# Proto1.net
KiCad netlist of a schematic drawn in EAGLE
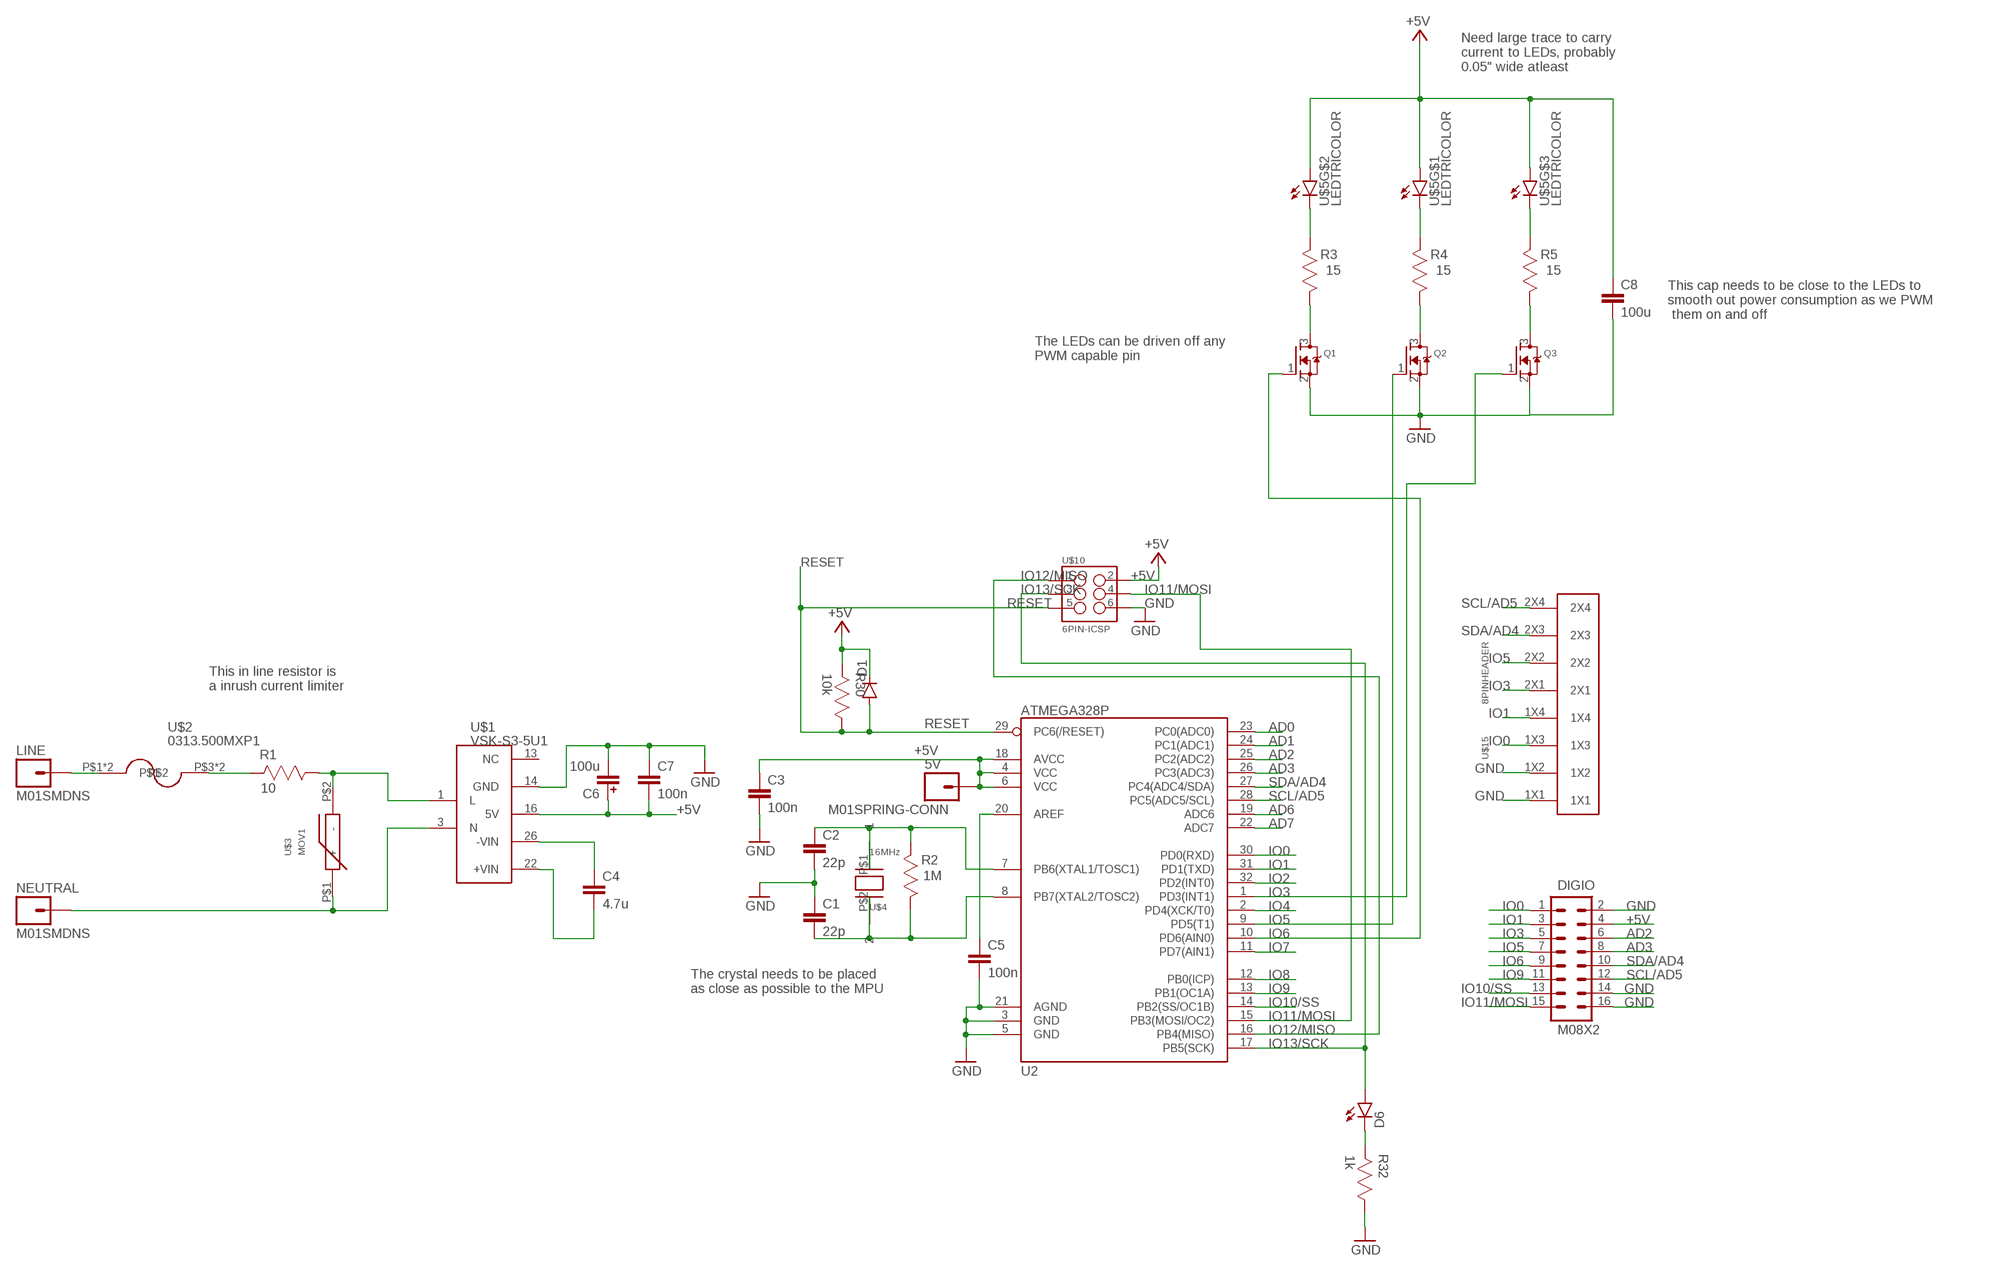
[diagram p0: schematic, sheet 1]

(export (version "E")
  (design (tool "Eeschema 10.0.6"))
  (components
    (comp (ref "5V")
      (value "M01SPRING-CONN")
      (footprint "eagle-import:SPRING-CONNECTOR")
      (libsource (lib "eagle-import") (part "M01SPRING-CONN"))
    )
    (comp (ref "C1")
      (value "22p")
      (footprint "eagle-import:0603-CAP")
      (libsource (lib "eagle-import") (part "CAP0603-CAP"))
    )
    (comp (ref "C2")
      (value "22p")
      (footprint "eagle-import:0603-CAP")
      (libsource (lib "eagle-import") (part "CAP0603-CAP"))
    )
    (comp (ref "C3")
      (value "100n")
      (footprint "eagle-import:0603-CAP")
      (libsource (lib "eagle-import") (part "CAP0603-CAP"))
    )
    (comp (ref "C4")
      (value "4.7u")
      (footprint "eagle-import:0603-CAP")
      (libsource (lib "eagle-import") (part "CAP0603-CAP"))
    )
    (comp (ref "C5")
      (value "100n")
      (footprint "eagle-import:0603-CAP")
      (libsource (lib "eagle-import") (part "CAP0603-CAP"))
    )
    (comp (ref "C6")
      (value "100u")
      (footprint "eagle-import:WXSERIES-SMDCAP")
      (libsource (lib "eagle-import") (part "SMDCAP1"))
    )
    (comp (ref "C7")
      (value "100n")
      (footprint "eagle-import:0603-CAP")
      (libsource (lib "eagle-import") (part "CAP0603-CAP"))
    )
    (comp (ref "C8")
      (value "100u")
      (footprint "eagle-import:0603-CAP")
      (libsource (lib "eagle-import") (part "CAP0603-CAP"))
    )
    (comp (ref "D1")
      (value "DIODE1N4148")
      (footprint "eagle-import:DIODE-1N4148")
      (libsource (lib "eagle-import") (part "DIODE1N4148"))
    )
    (comp (ref "D6")
      (value "LED-YELLOW0603")
      (footprint "eagle-import:LED-0603")
      (libsource (lib "eagle-import") (part "LED-YELLOW0603"))
    )
    (comp (ref "DIGIO")
      (value "M08X2")
      (footprint "eagle-import:2X8")
      (libsource (lib "eagle-import") (part "M08X2"))
    )
    (comp (ref "LINE")
      (value "M01SMDNS")
      (footprint "eagle-import:1X01NS")
      (libsource (lib "eagle-import") (part "M01SMDNS"))
    )
    (comp (ref "NEUTRAL")
      (value "M01SMDNS")
      (footprint "eagle-import:1X01NS")
      (libsource (lib "eagle-import") (part "M01SMDNS"))
    )
    (comp (ref "Q1")
      (value "MOSFET-NREFLOW")
      (footprint "eagle-import:SOT23")
      (libsource (lib "eagle-import") (part "MOSFET-NREFLOW"))
    )
    (comp (ref "Q2")
      (value "MOSFET-NREFLOW")
      (footprint "eagle-import:SOT23")
      (libsource (lib "eagle-import") (part "MOSFET-NREFLOW"))
    )
    (comp (ref "Q3")
      (value "MOSFET-NREFLOW")
      (footprint "eagle-import:SOT23")
      (libsource (lib "eagle-import") (part "MOSFET-NREFLOW"))
    )
    (comp (ref "R1")
      (value "10")
      (footprint "eagle-import:0603RESISTOR")
      (fields (field (name "MPN") "CRCW06031K21FKEA") (field (name "TOLERANCE") "± 1.0 %"))
      (libsource (lib "eagle-import") (part "0603RESISTOR1"))
    )
    (comp (ref "R2")
      (value "1M")
      (footprint "eagle-import:0603RESISTOR")
      (fields (field (name "MPN") "CRCW06031K21FKEA") (field (name "TOLERANCE") "± 1.0 %"))
      (libsource (lib "eagle-import") (part "0603RESISTOR1"))
    )
    (comp (ref "R3")
      (value "15")
      (footprint "eagle-import:0603RESISTOR")
      (fields (field (name "MPN") "CRCW06031K21FKEA") (field (name "TOLERANCE") "± 1.0 %"))
      (libsource (lib "eagle-import") (part "0603RESISTOR1"))
    )
    (comp (ref "R4")
      (value "15")
      (footprint "eagle-import:0603RESISTOR")
      (fields (field (name "MPN") "CRCW06031K21FKEA") (field (name "TOLERANCE") "± 1.0 %"))
      (libsource (lib "eagle-import") (part "0603RESISTOR1"))
    )
    (comp (ref "R5")
      (value "15")
      (footprint "eagle-import:0603RESISTOR")
      (fields (field (name "MPN") "CRCW06031K21FKEA") (field (name "TOLERANCE") "± 1.0 %"))
      (libsource (lib "eagle-import") (part "0603RESISTOR1"))
    )
    (comp (ref "R30")
      (value "10k")
      (footprint "eagle-import:0603RESISTOR")
      (fields (field (name "MPN") "CRCW06031K21FKEA") (field (name "TOLERANCE") "± 1.0 %"))
      (libsource (lib "eagle-import") (part "0603RESISTOR1"))
    )
    (comp (ref "R32")
      (value "1k")
      (footprint "eagle-import:0603RESISTOR")
      (fields (field (name "MPN") "CRCW06031K21FKEA") (field (name "TOLERANCE") "± 1.0 %"))
      (libsource (lib "eagle-import") (part "0603RESISTOR1"))
    )
    (comp (ref "U$1")
      (value "VSK-S3-5U1")
      (footprint "eagle-import:VSK-S3-DCAC")
      (libsource (lib "eagle-import") (part "VSK-S3-5U1"))
    )
    (comp (ref "U$2")
      (value "0313.500MXP1")
      (footprint "eagle-import:FUSEHOLDER0.25IN")
      (libsource (lib "eagle-import") (part "0313.500MXP1"))
    )
    (comp (ref "U$3")
      (value "MOV1")
      (footprint "eagle-import:MOV")
      (libsource (lib "eagle-import") (part "MOV1"))
    )
    (comp (ref "U$4")
      (value "16MHz")
      (footprint "eagle-import:SMDCRYSTAL")
      (libsource (lib "eagle-import") (part "SMDCRYSTAL"))
    )
    (comp (ref "U$5")
      (value "LEDTRICOLOR")
      (footprint "eagle-import:TRICOLORLED")
      (libsource (lib "eagle-import") (part "LEDTRICOLOR"))
    )
    (comp (ref "U$10")
      (value "6PIN-ICSP")
      (footprint "eagle-import:2X3-ICSP")
      (libsource (lib "eagle-import") (part "6PIN-ICSP"))
    )
    (comp (ref "U$15")
      (value "8PINHEADER")
      (footprint "eagle-import:HEADERSMDRIGHTANGLE4X2")
      (libsource (lib "eagle-import") (part "8PINHEADER"))
    )
    (comp (ref "U2")
      (value "ATMEGA328P")
      (footprint "eagle-import:TQFP32-08")
      (libsource (lib "eagle-import") (part "ATMEGA328_SMT"))
    )
  )
  (nets
    (net (code "1") (name "+5V") (class "Default")
      (node (ref "5V") (pin "P$2") (pinfunction "1_P$2") (pintype "passive"))
      (node (ref "C3") (pin "1") (pinfunction "1_1") (pintype "passive"))
      (node (ref "C6") (pin "POS") (pinfunction "POS_POS") (pintype "passive"))
      (node (ref "C7") (pin "2") (pinfunction "2_2") (pintype "passive"))
      (node (ref "C8") (pin "1") (pinfunction "1_1") (pintype "passive"))
      (node (ref "D1") (pin "C") (pinfunction "C_C") (pintype "passive"))
      (node (ref "DIGIO") (pin "4") (pinfunction "4_4") (pintype "passive"))
      (node (ref "R30") (pin "2") (pinfunction "2_2") (pintype "passive"))
      (node (ref "U$1") (pin "16") (pinfunction "5V_16") (pintype "bidirectional"))
      (node (ref "U$10") (pin "2") (pinfunction "+5V_2") (pintype "power_in"))
      (node (ref "U$5") (pin "A1") (pinfunction "A_A1") (pintype "passive"))
      (node (ref "U$5") (pin "A2") (pinfunction "A_A2") (pintype "passive"))
      (node (ref "U$5") (pin "A3") (pinfunction "A_A3") (pintype "passive"))
      (node (ref "U2") (pin "18") (pinfunction "AVCC_18") (pintype "bidirectional"))
      (node (ref "U2") (pin "4") (pinfunction "VCC_4") (pintype "bidirectional"))
      (node (ref "U2") (pin "6") (pinfunction "VCC_6") (pintype "bidirectional"))
    )
    (net (code "2") (name "/AD0") (class "Default")
      (node (ref "U2") (pin "23") (pinfunction "PC0(ADC0)_23") (pintype "bidirectional"))
    )
    (net (code "3") (name "/AD1") (class "Default")
      (node (ref "U2") (pin "24") (pinfunction "PC1(ADC1)_24") (pintype "bidirectional"))
    )
    (net (code "4") (name "/AD2") (class "Default")
      (node (ref "DIGIO") (pin "6") (pinfunction "6_6") (pintype "passive"))
      (node (ref "U2") (pin "25") (pinfunction "PC2(ADC2)_25") (pintype "bidirectional"))
    )
    (net (code "5") (name "/AD3") (class "Default")
      (node (ref "DIGIO") (pin "8") (pinfunction "8_8") (pintype "passive"))
      (node (ref "U2") (pin "26") (pinfunction "PC3(ADC3)_26") (pintype "bidirectional"))
    )
    (net (code "6") (name "/AD6") (class "Default")
      (node (ref "U2") (pin "19") (pinfunction "ADC6_19") (pintype "bidirectional"))
    )
    (net (code "7") (name "/AD7") (class "Default")
      (node (ref "U2") (pin "22") (pinfunction "ADC7_22") (pintype "bidirectional"))
    )
    (net (code "8") (name "/IO0") (class "Default")
      (node (ref "DIGIO") (pin "1") (pinfunction "1_1") (pintype "passive"))
      (node (ref "U$15") (pin "1X3") (pinfunction "1X3_1X3") (pintype "bidirectional"))
      (node (ref "U2") (pin "30") (pinfunction "PD0(RXD)_30") (pintype "bidirectional"))
    )
    (net (code "9") (name "/IO1") (class "Default")
      (node (ref "DIGIO") (pin "3") (pinfunction "3_3") (pintype "passive"))
      (node (ref "U$15") (pin "1X4") (pinfunction "1X4_1X4") (pintype "bidirectional"))
      (node (ref "U2") (pin "31") (pinfunction "PD1(TXD)_31") (pintype "bidirectional"))
    )
    (net (code "10") (name "/IO2") (class "Default")
      (node (ref "U2") (pin "32") (pinfunction "PD2(INT0)_32") (pintype "bidirectional"))
    )
    (net (code "11") (name "/IO3") (class "Default")
      (node (ref "DIGIO") (pin "5") (pinfunction "5_5") (pintype "passive"))
      (node (ref "Q3") (pin "1") (pinfunction "G_1") (pintype "bidirectional"))
      (node (ref "U$15") (pin "2X1") (pinfunction "2X1_2X1") (pintype "bidirectional"))
      (node (ref "U2") (pin "1") (pinfunction "PD3(INT1)_1") (pintype "bidirectional"))
    )
    (net (code "12") (name "/IO4") (class "Default")
      (node (ref "U2") (pin "2") (pinfunction "PD4(XCK/T0)_2") (pintype "bidirectional"))
    )
    (net (code "13") (name "/IO5") (class "Default")
      (node (ref "DIGIO") (pin "7") (pinfunction "7_7") (pintype "passive"))
      (node (ref "Q2") (pin "1") (pinfunction "G_1") (pintype "bidirectional"))
      (node (ref "U$15") (pin "2X2") (pinfunction "2X2_2X2") (pintype "bidirectional"))
      (node (ref "U2") (pin "9") (pinfunction "PD5(T1)_9") (pintype "bidirectional"))
    )
    (net (code "14") (name "/IO6") (class "Default")
      (node (ref "DIGIO") (pin "9") (pinfunction "9_9") (pintype "passive"))
      (node (ref "Q1") (pin "1") (pinfunction "G_1") (pintype "bidirectional"))
      (node (ref "U2") (pin "10") (pinfunction "PD6(AIN0)_10") (pintype "bidirectional"))
    )
    (net (code "15") (name "/IO7") (class "Default")
      (node (ref "U2") (pin "11") (pinfunction "PD7(AIN1)_11") (pintype "bidirectional"))
    )
    (net (code "16") (name "/IO8") (class "Default")
      (node (ref "U2") (pin "12") (pinfunction "PB0(ICP)_12") (pintype "bidirectional"))
    )
    (net (code "17") (name "/IO9") (class "Default")
      (node (ref "DIGIO") (pin "11") (pinfunction "11_11") (pintype "passive"))
      (node (ref "U2") (pin "13") (pinfunction "PB1(OC1A)_13") (pintype "bidirectional"))
    )
    (net (code "18") (name "/IO10{slash}SS") (class "Default")
      (node (ref "DIGIO") (pin "13") (pinfunction "13_13") (pintype "passive"))
      (node (ref "U2") (pin "14") (pinfunction "PB2(SS/OC1B)_14") (pintype "bidirectional"))
    )
    (net (code "19") (name "/IO11{slash}MOSI") (class "Default")
      (node (ref "DIGIO") (pin "15") (pinfunction "15_15") (pintype "passive"))
      (node (ref "U$10") (pin "4") (pinfunction "MOSI_4") (pintype "bidirectional"))
      (node (ref "U2") (pin "15") (pinfunction "PB3(MOSI/OC2)_15") (pintype "bidirectional"))
    )
    (net (code "20") (name "/IO12{slash}MISO") (class "Default")
      (node (ref "U$10") (pin "1") (pinfunction "MISO_1") (pintype "bidirectional"))
      (node (ref "U2") (pin "16") (pinfunction "PB4(MISO)_16") (pintype "bidirectional"))
    )
    (net (code "21") (name "/IO13{slash}SCK") (class "Default")
      (node (ref "D6") (pin "A") (pinfunction "A_A") (pintype "passive"))
      (node (ref "U$10") (pin "3") (pinfunction "SCK_3") (pintype "bidirectional"))
      (node (ref "U2") (pin "17") (pinfunction "PB5(SCK)_17") (pintype "bidirectional"))
    )
    (net (code "22") (name "/RESET") (class "Default")
      (node (ref "D1") (pin "A") (pinfunction "A_A") (pintype "passive"))
      (node (ref "R30") (pin "1") (pinfunction "1_1") (pintype "passive"))
      (node (ref "U$10") (pin "5") (pinfunction "RESET_5") (pintype "bidirectional"))
      (node (ref "U2") (pin "29") (pinfunction "PC6(/RESET)_29") (pintype "bidirectional"))
    )
    (net (code "23") (name "/SCL{slash}AD5") (class "Default")
      (node (ref "DIGIO") (pin "12") (pinfunction "12_12") (pintype "passive"))
      (node (ref "U$15") (pin "2X4") (pinfunction "2X4_2X4") (pintype "bidirectional"))
      (node (ref "U2") (pin "28") (pinfunction "PC5(ADC5/SCL)_28") (pintype "bidirectional"))
    )
    (net (code "24") (name "/SDA{slash}AD4") (class "Default")
      (node (ref "DIGIO") (pin "10") (pinfunction "10_10") (pintype "passive"))
      (node (ref "U$15") (pin "2X3") (pinfunction "2X3_2X3") (pintype "bidirectional"))
      (node (ref "U2") (pin "27") (pinfunction "PC4(ADC4/SDA)_27") (pintype "bidirectional"))
    )
    (net (code "25") (name "GND") (class "Default")
      (node (ref "C1") (pin "1") (pinfunction "1_1") (pintype "passive"))
      (node (ref "C2") (pin "2") (pinfunction "2_2") (pintype "passive"))
      (node (ref "C3") (pin "2") (pinfunction "2_2") (pintype "passive"))
      (node (ref "C5") (pin "2") (pinfunction "2_2") (pintype "passive"))
      (node (ref "C6") (pin "NEG") (pinfunction "NEG_NEG") (pintype "passive"))
      (node (ref "C7") (pin "1") (pinfunction "1_1") (pintype "passive"))
      (node (ref "C8") (pin "2") (pinfunction "2_2") (pintype "passive"))
      (node (ref "DIGIO") (pin "14") (pinfunction "14_14") (pintype "passive"))
      (node (ref "DIGIO") (pin "16") (pinfunction "16_16") (pintype "passive"))
      (node (ref "DIGIO") (pin "2") (pinfunction "2_2") (pintype "passive"))
      (node (ref "Q1") (pin "2") (pinfunction "S_2") (pintype "bidirectional"))
      (node (ref "Q2") (pin "2") (pinfunction "S_2") (pintype "bidirectional"))
      (node (ref "Q3") (pin "2") (pinfunction "S_2") (pintype "bidirectional"))
      (node (ref "R32") (pin "1") (pinfunction "1_1") (pintype "passive"))
      (node (ref "U$1") (pin "14") (pinfunction "GND_14") (pintype "bidirectional"))
      (node (ref "U$10") (pin "6") (pinfunction "GND_6") (pintype "power_in"))
      (node (ref "U$15") (pin "1X1") (pinfunction "1X1_1X1") (pintype "bidirectional"))
      (node (ref "U$15") (pin "1X2") (pinfunction "1X2_1X2") (pintype "bidirectional"))
      (node (ref "U2") (pin "21") (pinfunction "AGND_21") (pintype "bidirectional"))
      (node (ref "U2") (pin "3") (pinfunction "GND_3") (pintype "bidirectional"))
      (node (ref "U2") (pin "5") (pinfunction "GND_5") (pintype "bidirectional"))
    )
    (net (code "26") (name "Net-(D6-PadC)") (class "Default")
      (node (ref "D6") (pin "C") (pinfunction "C_C") (pintype "passive"))
      (node (ref "R32") (pin "2") (pinfunction "2_2") (pintype "passive"))
    )
    (net (code "27") (name "Net-(LINE-Pad1)") (class "Default")
      (node (ref "LINE") (pin "1") (pinfunction "1_1") (pintype "passive"))
      (node (ref "U$2") (pin "P$1") (pinfunction "P$1_P$1") (pintype "bidirectional"))
      (node (ref "U$2") (pin "P$2") (pinfunction "P$1_P$2") (pintype "bidirectional"))
    )
    (net (code "28") (name "Net-(Q1-D)") (class "Default")
      (node (ref "Q1") (pin "3") (pinfunction "D_3") (pintype "bidirectional"))
      (node (ref "R3") (pin "1") (pinfunction "1_1") (pintype "passive"))
    )
    (net (code "29") (name "Net-(Q2-D)") (class "Default")
      (node (ref "Q2") (pin "3") (pinfunction "D_3") (pintype "bidirectional"))
      (node (ref "R4") (pin "1") (pinfunction "1_1") (pintype "passive"))
    )
    (net (code "30") (name "Net-(Q3-D)") (class "Default")
      (node (ref "Q3") (pin "3") (pinfunction "D_3") (pintype "bidirectional"))
      (node (ref "R5") (pin "1") (pinfunction "1_1") (pintype "passive"))
    )
    (net (code "31") (name "Net-(R1-Pad2)") (class "Default")
      (node (ref "R1") (pin "2") (pinfunction "2_2") (pintype "passive"))
      (node (ref "U$2") (pin "P$3") (pinfunction "P$2_P$3") (pintype "bidirectional"))
      (node (ref "U$2") (pin "P$4") (pinfunction "P$2_P$4") (pintype "bidirectional"))
    )
    (net (code "32") (name "Net-(U$1-+VIN)") (class "Default")
      (node (ref "C4") (pin "2") (pinfunction "2_2") (pintype "passive"))
      (node (ref "U$1") (pin "22") (pinfunction "+VIN_22") (pintype "bidirectional"))
    )
    (net (code "33") (name "Net-(U$1--VIN)") (class "Default")
      (node (ref "C4") (pin "1") (pinfunction "1_1") (pintype "passive"))
      (node (ref "U$1") (pin "26") (pinfunction "-VIN_26") (pintype "bidirectional"))
    )
    (net (code "34") (name "Net-(U$1-L)") (class "Default")
      (node (ref "R1") (pin "1") (pinfunction "1_1") (pintype "passive"))
      (node (ref "U$1") (pin "1") (pinfunction "L_1") (pintype "bidirectional"))
      (node (ref "U$3") (pin "P$2") (pinfunction "-_P$2") (pintype "bidirectional"))
    )
    (net (code "35") (name "Net-(U$1-N)") (class "Default")
      (node (ref "NEUTRAL") (pin "1") (pinfunction "1_1") (pintype "passive"))
      (node (ref "U$1") (pin "3") (pinfunction "N_3") (pintype "bidirectional"))
      (node (ref "U$3") (pin "P$1") (pinfunction "+_P$1") (pintype "bidirectional"))
    )
    (net (code "36") (name "Net-(U$4-1)") (class "Default")
      (node (ref "C2") (pin "1") (pinfunction "1_1") (pintype "passive"))
      (node (ref "R2") (pin "2") (pinfunction "2_2") (pintype "passive"))
      (node (ref "U$4") (pin "P$1") (pinfunction "1_P$1") (pintype "bidirectional"))
      (node (ref "U2") (pin "7") (pinfunction "PB6(XTAL1/TOSC1)_7") (pintype "bidirectional"))
    )
    (net (code "37") (name "Net-(U$4-2)") (class "Default")
      (node (ref "C1") (pin "2") (pinfunction "2_2") (pintype "passive"))
      (node (ref "R2") (pin "1") (pinfunction "1_1") (pintype "passive"))
      (node (ref "U$4") (pin "P$2") (pinfunction "2_P$2") (pintype "bidirectional"))
      (node (ref "U2") (pin "8") (pinfunction "PB7(XTAL2/TOSC2)_8") (pintype "bidirectional"))
    )
    (net (code "38") (name "Net-(U$5A-C)") (class "Default")
      (node (ref "R4") (pin "2") (pinfunction "2_2") (pintype "passive"))
      (node (ref "U$5") (pin "C1") (pinfunction "C_C1") (pintype "passive"))
    )
    (net (code "39") (name "Net-(U$5B-C)") (class "Default")
      (node (ref "R3") (pin "2") (pinfunction "2_2") (pintype "passive"))
      (node (ref "U$5") (pin "C2") (pinfunction "C_C2") (pintype "passive"))
    )
    (net (code "40") (name "Net-(U$5C-C)") (class "Default")
      (node (ref "R5") (pin "2") (pinfunction "2_2") (pintype "passive"))
      (node (ref "U$5") (pin "C3") (pinfunction "C_C3") (pintype "passive"))
    )
    (net (code "41") (name "Net-(U2-AREF)") (class "Default")
      (node (ref "C5") (pin "1") (pinfunction "1_1") (pintype "passive"))
      (node (ref "U2") (pin "20") (pinfunction "AREF_20") (pintype "bidirectional"))
    )
    (net (code "42") (name "unconnected-(U$1-NC-Pad13)") (class "Default")
      (node (ref "U$1") (pin "13") (pinfunction "NC_13") (pintype "no_connect"))
    )
  )
)
